# Display.net
KiCad netlist of a schematic drawn in Altium Designer
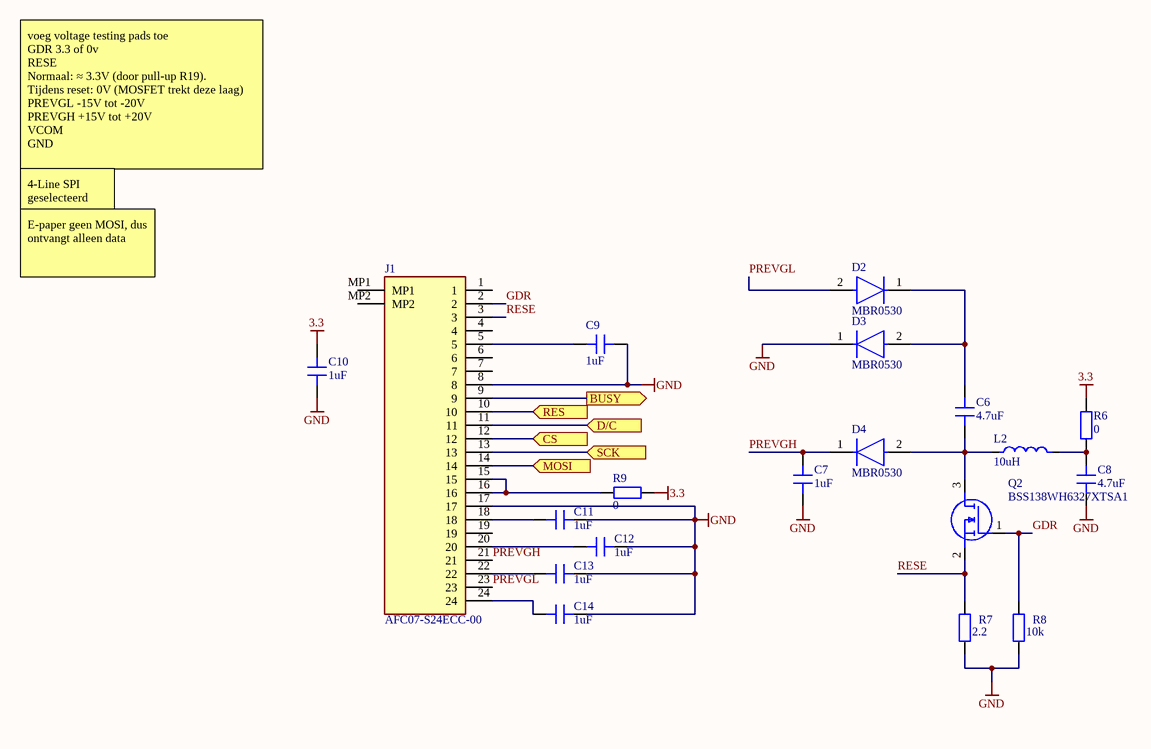
[diagram p0: Display.SchDoc]

(export (version "E")
  (design (tool "Eeschema 10.0.6"))
  (components
    (comp (ref "C6") (value "4.7uF") (footprint "0603_CAP") (libsource (lib "passive_components") (part "C")))
    (comp (ref "C7") (value "1uF") (footprint "0603_CAP") (libsource (lib "passive_components") (part "C")))
    (comp (ref "C8") (value "4.7uF") (footprint "0603_CAP") (libsource (lib "passive_components") (part "C")))
    (comp (ref "C9") (value "1uF") (footprint "0603_CAP") (libsource (lib "passive_components") (part "C")))
    (comp (ref "C10") (value "1uF") (footprint "0603_CAP") (libsource (lib "passive_components") (part "C")))
    (comp (ref "C11") (value "1uF") (footprint "0603_CAP") (libsource (lib "passive_components") (part "C")))
    (comp (ref "C12") (value "1uF") (footprint "0603_CAP") (libsource (lib "passive_components") (part "C")))
    (comp (ref "C13") (value "1uF") (footprint "0603_CAP") (libsource (lib "passive_components") (part "C")))
    (comp (ref "C14") (value "1uF") (footprint "0603_CAP") (libsource (lib "passive_components") (part "C")))
    (comp (ref "D2")
      (value "MBR0530")
      (footprint "SOD3716X135N")
      (description "1N4148W-G3-08 Rectifier Diode, 1 Phase, 1 Element, 0.15A, 100V V(RRM), Silicon")
      (libsource (lib "Diode") (part "CMP-00030-46456310-1"))
    )
    (comp (ref "D3")
      (value "MBR0530")
      (footprint "SOD3716X135N")
      (description "1N4148W-G3-08 Rectifier Diode, 1 Phase, 1 Element, 0.15A, 100V V(RRM), Silicon")
      (libsource (lib "Diode") (part "CMP-00030-46456310-1"))
    )
    (comp (ref "D4")
      (value "MBR0530")
      (footprint "SOD3716X135N")
      (description "1N4148W-G3-08 Rectifier Diode, 1 Phase, 1 Element, 0.15A, 100V V(RRM), Silicon")
      (libsource (lib "Diode") (part "CMP-00030-46456310-1"))
    )
    (comp (ref "J1")
      (value "AFC07-S24ECC-00")
      (footprint "AFC07S24ECC00")
      (description "Connector")
      (libsource (lib "Display_Connector") (part "AFC07-S24ECC-00"))
    )
    (comp (ref "L2")
      (value "10uH")
      (footprint "NRS5040T3R3NMGJV")
      (libsource (lib "passive_components") (part "coil"))
    )
    (comp (ref "Q2")
      (value "BSS138WH6327XTSA1")
      (footprint "SOT65P210X110-3N")
      (description "MOSFET (N-Channel)")
      (fields (field (name "MOUSER PART NUMBER") "726-BSS138WH6327XTSA"))
      (libsource (lib "N-channel mosfet") (part "BSS138WH6327XTSA1"))
    )
    (comp (ref "R6") (value "0") (footprint "0603") (libsource (lib "passive_components") (part "R")))
    (comp (ref "R7") (value "2.2") (footprint "0402_RES") (libsource (lib "passive_components") (part "R")))
    (comp (ref "R8") (value "10k") (footprint "0402_RES") (libsource (lib "passive_components") (part "R")))
    (comp (ref "R9") (value "0") (footprint "0603") (libsource (lib "passive_components") (part "R")))
  )
  (nets
    (net (code "1") (name "/BUSY") (class "Default")
      (node (ref "J1") (pin "9") (pinfunction "9_9") (pintype "passive"))
    )
    (net (code "2") (name "/CS") (class "Default")
      (node (ref "J1") (pin "12") (pinfunction "12_12") (pintype "passive"))
    )
    (net (code "3") (name "/D{slash}C") (class "Default")
      (node (ref "J1") (pin "11") (pinfunction "11_11") (pintype "passive"))
    )
    (net (code "4") (name "/GDR") (class "Default")
      (node (ref "J1") (pin "2") (pinfunction "2_2") (pintype "passive"))
      (node (ref "Q2") (pin "1") (pinfunction "G_1") (pintype "passive"))
      (node (ref "R8") (pin "1") (pinfunction "25_1") (pintype "passive"))
    )
    (net (code "5") (name "/MOSI") (class "Default")
      (node (ref "J1") (pin "14") (pinfunction "14_14") (pintype "passive"))
    )
    (net (code "6") (name "/PREVGH") (class "Default")
      (node (ref "C7") (pin "2") (pinfunction "28_2") (pintype "passive"))
      (node (ref "D4") (pin "1") (pinfunction "C_1") (pintype "passive"))
      (node (ref "J1") (pin "21") (pinfunction "21_21") (pintype "passive"))
    )
    (net (code "7") (name "/PREVGL") (class "Default")
      (node (ref "D2") (pin "2") (pinfunction "A_2") (pintype "passive"))
      (node (ref "J1") (pin "23") (pinfunction "23_23") (pintype "passive"))
    )
    (net (code "8") (name "/RES") (class "Default")
      (node (ref "J1") (pin "10") (pinfunction "10_10") (pintype "passive"))
    )
    (net (code "9") (name "/RESE") (class "Default")
      (node (ref "J1") (pin "3") (pinfunction "3_3") (pintype "passive"))
      (node (ref "Q2") (pin "2") (pinfunction "S_2") (pintype "passive"))
      (node (ref "R7") (pin "2") (pinfunction "26_2") (pintype "passive"))
    )
    (net (code "10") (name "/SCK") (class "Default")
      (node (ref "J1") (pin "13") (pinfunction "13_13") (pintype "passive"))
    )
    (net (code "11") (name "3.3") (class "Default")
      (node (ref "C10") (pin "2") (pinfunction "28_2") (pintype "passive"))
      (node (ref "R6") (pin "1") (pinfunction "25_1") (pintype "passive"))
      (node (ref "R9") (pin "1") (pinfunction "25_1") (pintype "passive"))
    )
    (net (code "12") (name "GND") (class "Default")
      (node (ref "C10") (pin "1") (pinfunction "1_1") (pintype "passive"))
      (node (ref "C11") (pin "2") (pinfunction "28_2") (pintype "passive"))
      (node (ref "C12") (pin "2") (pinfunction "28_2") (pintype "passive"))
      (node (ref "C13") (pin "2") (pinfunction "28_2") (pintype "passive"))
      (node (ref "C14") (pin "2") (pinfunction "28_2") (pintype "passive"))
      (node (ref "C7") (pin "1") (pinfunction "1_1") (pintype "passive"))
      (node (ref "C8") (pin "1") (pinfunction "1_1") (pintype "passive"))
      (node (ref "C9") (pin "1") (pinfunction "1_1") (pintype "passive"))
      (node (ref "D3") (pin "1") (pinfunction "C_1") (pintype "passive"))
      (node (ref "J1") (pin "17") (pinfunction "17_17") (pintype "passive"))
      (node (ref "J1") (pin "8") (pinfunction "8_8") (pintype "passive"))
      (node (ref "R7") (pin "1") (pinfunction "25_1") (pintype "passive"))
      (node (ref "R8") (pin "2") (pinfunction "26_2") (pintype "passive"))
    )
    (net (code "13") (name "Net-(C6-28)") (class "Default")
      (node (ref "C6") (pin "2") (pinfunction "28_2") (pintype "passive"))
      (node (ref "D2") (pin "1") (pinfunction "C_1") (pintype "passive"))
      (node (ref "D3") (pin "2") (pinfunction "A_2") (pintype "passive"))
    )
    (net (code "14") (name "Net-(C8-28)") (class "Default")
      (node (ref "C8") (pin "2") (pinfunction "28_2") (pintype "passive"))
      (node (ref "L2") (pin "2") (pinfunction "2_2") (pintype "passive"))
      (node (ref "R6") (pin "2") (pinfunction "26_2") (pintype "passive"))
    )
    (net (code "15") (name "Net-(C9-28)") (class "Default")
      (node (ref "C9") (pin "2") (pinfunction "28_2") (pintype "passive"))
      (node (ref "J1") (pin "5") (pinfunction "5_5") (pintype "passive"))
    )
    (net (code "16") (name "Net-(C11-Pad1)") (class "Default")
      (node (ref "C11") (pin "1") (pinfunction "1_1") (pintype "passive"))
      (node (ref "J1") (pin "18") (pinfunction "18_18") (pintype "passive"))
    )
    (net (code "17") (name "Net-(C12-Pad1)") (class "Default")
      (node (ref "C12") (pin "1") (pinfunction "1_1") (pintype "passive"))
      (node (ref "J1") (pin "20") (pinfunction "20_20") (pintype "passive"))
    )
    (net (code "18") (name "Net-(C13-Pad1)") (class "Default")
      (node (ref "C13") (pin "1") (pinfunction "1_1") (pintype "passive"))
      (node (ref "J1") (pin "22") (pinfunction "22_22") (pintype "passive"))
    )
    (net (code "19") (name "Net-(C14-Pad1)") (class "Default")
      (node (ref "C14") (pin "1") (pinfunction "1_1") (pintype "passive"))
      (node (ref "J1") (pin "24") (pinfunction "24_24") (pintype "passive"))
    )
    (net (code "20") (name "Net-(D4-A)") (class "Default")
      (node (ref "C6") (pin "1") (pinfunction "1_1") (pintype "passive"))
      (node (ref "D4") (pin "2") (pinfunction "A_2") (pintype "passive"))
      (node (ref "L2") (pin "1") (pinfunction "1_1") (pintype "passive"))
      (node (ref "Q2") (pin "3") (pinfunction "D_3") (pintype "passive"))
    )
    (net (code "21") (name "Net-(R9-26)") (class "Default")
      (node (ref "J1") (pin "15") (pinfunction "15_15") (pintype "passive"))
      (node (ref "J1") (pin "16") (pinfunction "16_16") (pintype "passive"))
      (node (ref "R9") (pin "2") (pinfunction "26_2") (pintype "passive"))
    )
    (net (code "22") (name "unconnected-(J1-Pad1)") (class "Default")
      (node (ref "J1") (pin "1") (pinfunction "1_1") (pintype "passive"))
    )
    (net (code "23") (name "unconnected-(J1-Pad4)") (class "Default")
      (node (ref "J1") (pin "4") (pinfunction "4_4") (pintype "passive"))
    )
    (net (code "24") (name "unconnected-(J1-Pad6)") (class "Default")
      (node (ref "J1") (pin "6") (pinfunction "6_6") (pintype "passive"))
    )
    (net (code "25") (name "unconnected-(J1-Pad7)") (class "Default")
      (node (ref "J1") (pin "7") (pinfunction "7_7") (pintype "passive"))
    )
    (net (code "26") (name "unconnected-(J1-Pad19)") (class "Default")
      (node (ref "J1") (pin "19") (pinfunction "19_19") (pintype "passive"))
    )
    (net (code "27") (name "unconnected-(J1-PadMP1)") (class "Default")
      (node (ref "J1") (pin "MP1") (pinfunction "MP1_MP1") (pintype "passive"))
    )
    (net (code "28") (name "unconnected-(J1-PadMP2)") (class "Default")
      (node (ref "J1") (pin "MP2") (pinfunction "MP2_MP2") (pintype "passive"))
    )
  )
)
